# TPS61099x.net
KiCad netlist of a schematic drawn in EAGLE
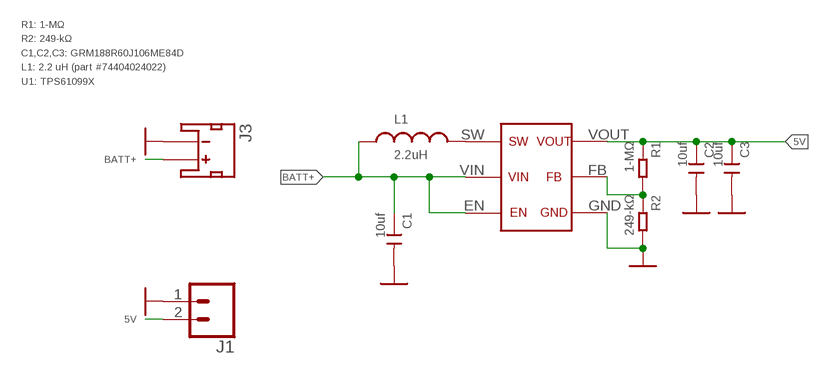
[diagram p0: schematic, sheet 1]

(export (version "E")
  (design (tool "Eeschema 10.0.6"))
  (components
    (comp (ref "C1")
      (value "10uf")
      (footprint "eagle-import:C0805")
      (fields (field (name "MPN") "CC0805MKX5R5BB226"))
      (libsource (lib "eagle-import") (part "CERAMIC-22UF-6.3V-20%-X5R(0805)"))
    )
    (comp (ref "C2")
      (value "10uf")
      (footprint "eagle-import:C0805")
      (fields (field (name "MPN") "CC0805MKX5R5BB226"))
      (libsource (lib "eagle-import") (part "CERAMIC-22UF-6.3V-20%-X5R(0805)"))
    )
    (comp (ref "C3")
      (value "10uf")
      (footprint "eagle-import:C0805")
      (fields (field (name "MPN") "CC0805MKX5R5BB226"))
      (libsource (lib "eagle-import") (part "CERAMIC-22UF-6.3V-20%-X5R(0805)"))
    )
    (comp (ref "J1")
      (value "CONN_02PTH4")
      (footprint "eagle-import:1X02_XTRA_BIG")
      (libsource (lib "eagle-import") (part "CONN_02PTH4"))
    )
    (comp (ref "J3")
      (value "Batt Conn")
      (footprint "eagle-import:JST-2-SMD")
      (libsource (lib "eagle-import") (part "JST_2MM_MALE"))
    )
    (comp (ref "L1")
      (value "2.2uH")
      (footprint "eagle-import:WE-LQS_2512")
      (libsource (lib "eagle-import") (part "WE-LQS_2512_74404024022"))
    )
    (comp (ref "R1")
      (value "1-MΩ")
      (footprint "eagle-import:R0805")
      (fields (field (name "MPN") "RL0805JR-070R1L"))
      (libsource (lib "eagle-import") (part "SMD-RES-0.1R-5%-1/8W(0805)"))
    )
    (comp (ref "R2")
      (value "249-kΩ")
      (footprint "eagle-import:R0805")
      (fields (field (name "MPN") "RL0805JR-070R1L"))
      (libsource (lib "eagle-import") (part "SMD-RES-0.1R-5%-1/8W(0805)"))
    )
    (comp (ref "U$1")
      (value "TPS61099X")
      (footprint "eagle-import:TPS61099X")
      (libsource (lib "eagle-import") (part "TPS61099X"))
    )
  )
  (nets
    (net (code "1") (name "5V") (class "Default")
      (node (ref "C2") (pin "1") (pinfunction "1_1") (pintype "passive"))
      (node (ref "C3") (pin "1") (pinfunction "1_1") (pintype "passive"))
      (node (ref "J1") (pin "2") (pinfunction "2_2") (pintype "passive"))
      (node (ref "R1") (pin "1") (pinfunction "1_1") (pintype "passive"))
      (node (ref "U$1") (pin "VOUT") (pinfunction "VOUT_VOUT") (pintype "bidirectional"))
    )
    (net (code "2") (name "BATT+") (class "Default")
      (node (ref "C1") (pin "1") (pinfunction "1_1") (pintype "passive"))
      (node (ref "J3") (pin "2") (pinfunction "+_2") (pintype "bidirectional"))
      (node (ref "L1") (pin "1") (pinfunction "1_1") (pintype "passive"))
      (node (ref "U$1") (pin "EN") (pinfunction "EN_EN") (pintype "bidirectional"))
      (node (ref "U$1") (pin "VIN") (pinfunction "VIN_VIN") (pintype "bidirectional"))
    )
    (net (code "3") (name "GND") (class "Default")
      (node (ref "C1") (pin "2") (pinfunction "2_2") (pintype "passive"))
      (node (ref "C2") (pin "2") (pinfunction "2_2") (pintype "passive"))
      (node (ref "C3") (pin "2") (pinfunction "2_2") (pintype "passive"))
      (node (ref "J1") (pin "1") (pinfunction "1_1") (pintype "passive"))
      (node (ref "J3") (pin "1") (pinfunction "-_1") (pintype "bidirectional"))
      (node (ref "R2") (pin "2") (pinfunction "2_2") (pintype "passive"))
      (node (ref "U$1") (pin "GND") (pinfunction "GND_GND") (pintype "bidirectional"))
    )
    (net (code "4") (name "Net-(L1-Pad2)") (class "Default")
      (node (ref "L1") (pin "2") (pinfunction "2_2") (pintype "passive"))
      (node (ref "U$1") (pin "SW") (pinfunction "SW_SW") (pintype "bidirectional"))
    )
    (net (code "5") (name "Net-(R1-Pad2)") (class "Default")
      (node (ref "R1") (pin "2") (pinfunction "2_2") (pintype "passive"))
      (node (ref "R2") (pin "1") (pinfunction "1_1") (pintype "passive"))
      (node (ref "U$1") (pin "FB") (pinfunction "FB_FB") (pintype "bidirectional"))
    )
    (net (code "6") (name "unconnected-(J3-PAD1-PadNC1)") (class "Default")
      (node (ref "J3") (pin "NC1") (pinfunction "PAD1_NC1") (pintype "bidirectional"))
    )
    (net (code "7") (name "unconnected-(J3-PAD2-PadNC2)") (class "Default")
      (node (ref "J3") (pin "NC2") (pinfunction "PAD2_NC2") (pintype "bidirectional"))
    )
  )
)
